# Spring2020V1_6.net
KiCad netlist of a schematic drawn in EAGLE
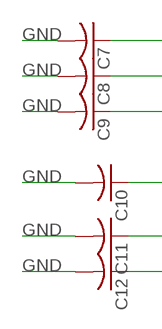
[diagram p0: schematic, sheet 1, part 1 of 2]
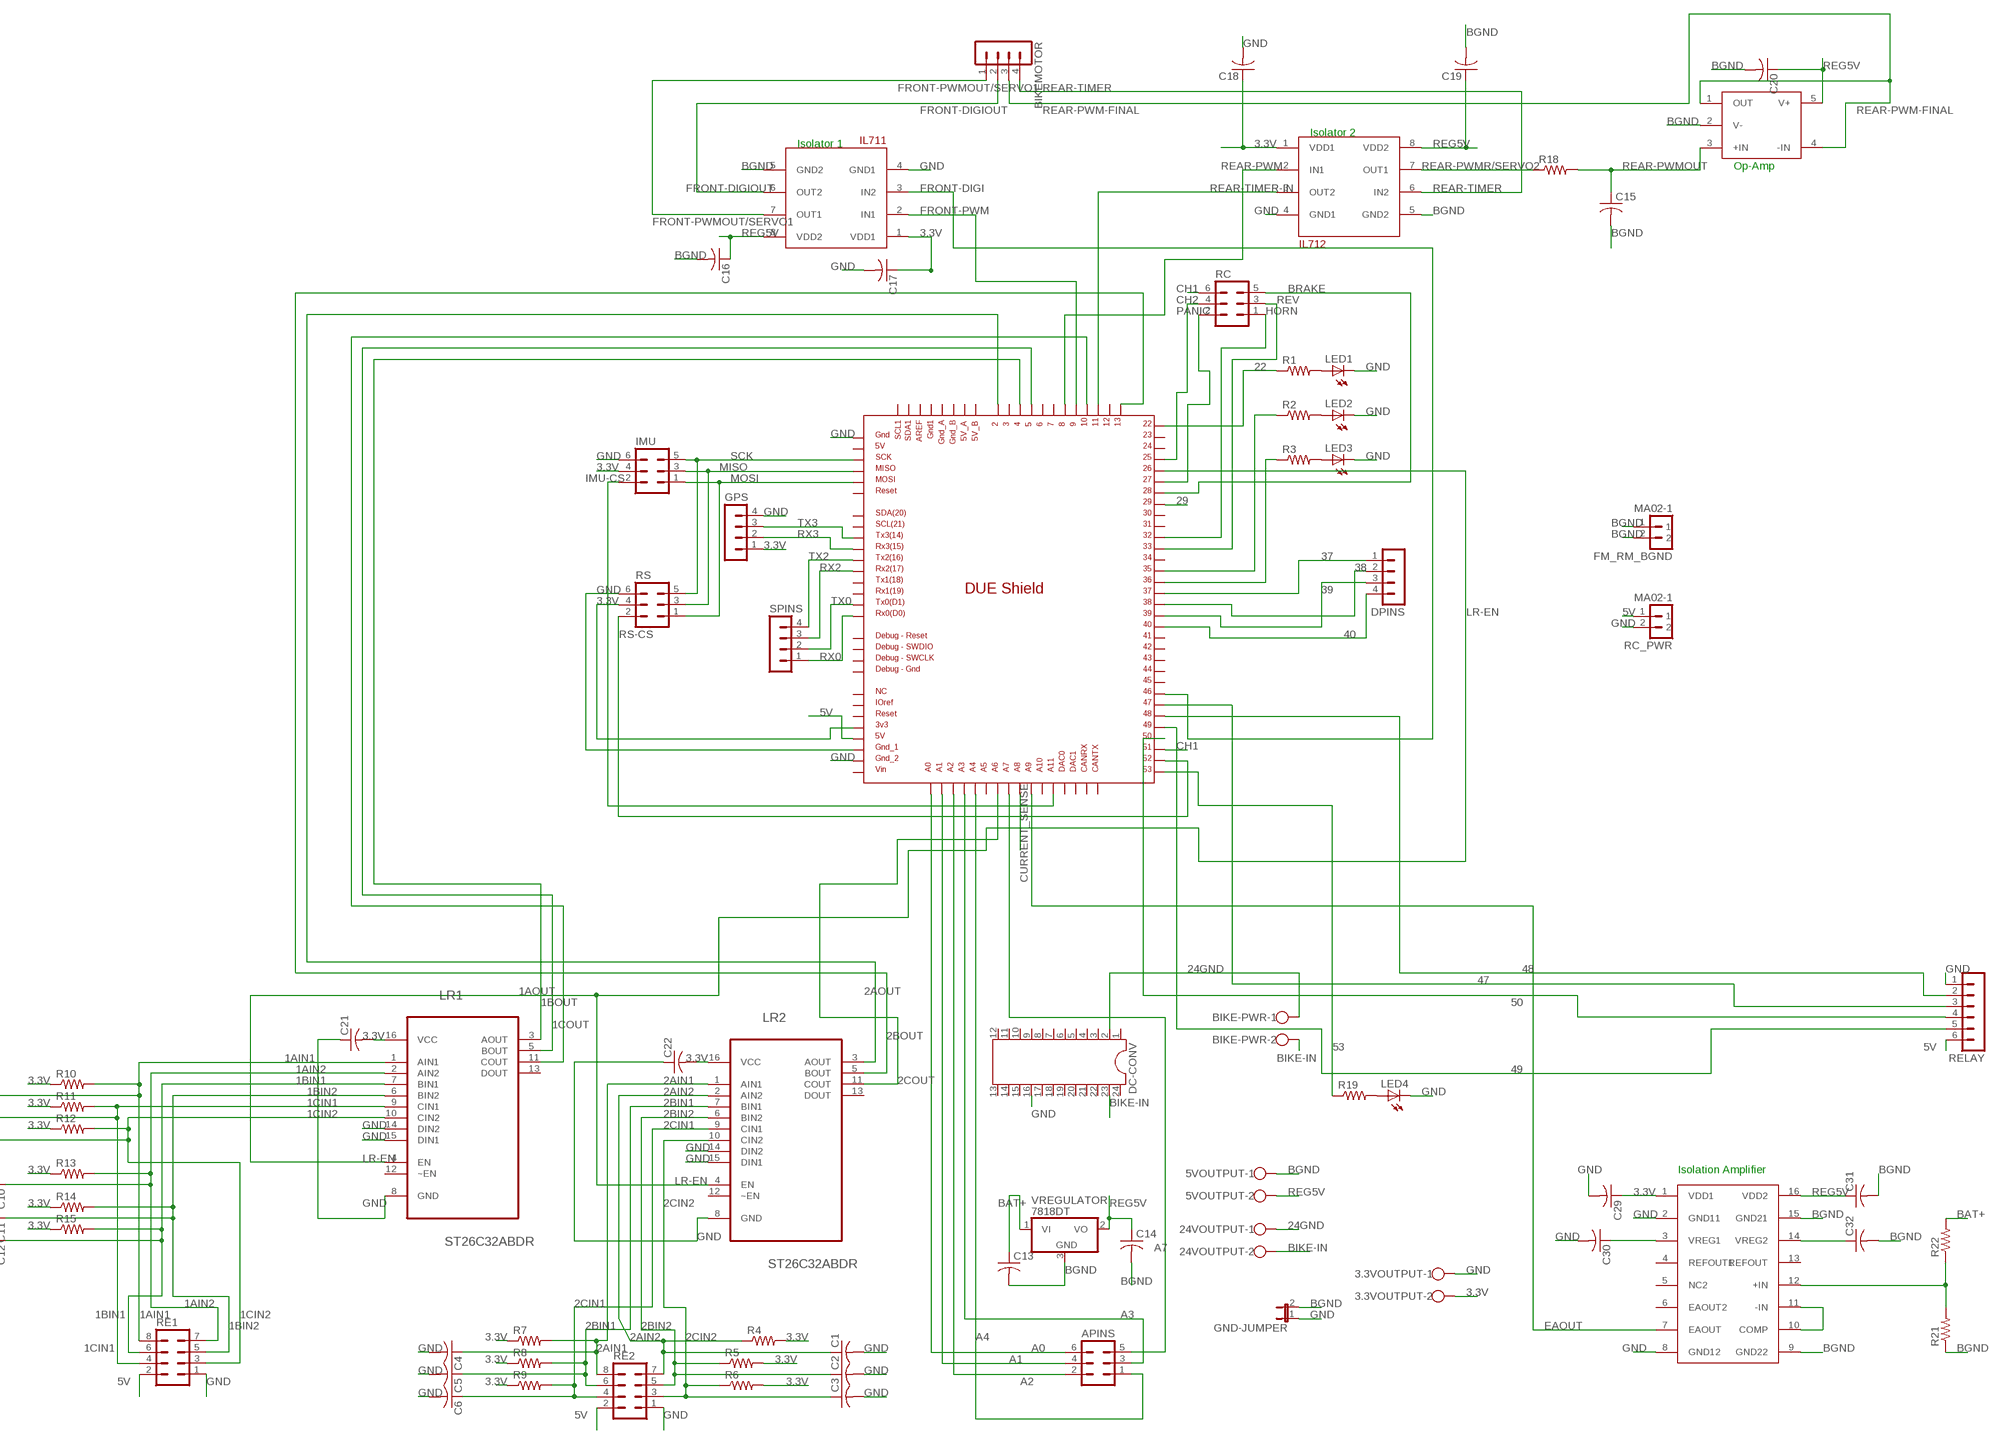
[diagram p1: schematic, sheet 1, part 2 of 2]

(export (version "E")
  (design (tool "Eeschema 10.0.6"))
  (components
    (comp (ref "3.3VOUTPUT")
      (value "W237-102")
      (footprint "eagle-import:W237-102")
      (fields (field (name "MPN") "237-102"))
      (libsource (lib "eagle-import") (part "W237-102"))
    )
    (comp (ref "5VOUTPUT")
      (value "W237-102")
      (footprint "eagle-import:W237-102")
      (fields (field (name "MPN") "237-102"))
      (libsource (lib "eagle-import") (part "W237-102"))
    )
    (comp (ref "24VOUTPUT")
      (value "W237-102")
      (footprint "eagle-import:W237-102")
      (fields (field (name "MPN") "237-102"))
      (libsource (lib "eagle-import") (part "W237-102"))
    )
    (comp (ref "APINS")
      (value "MA03-2")
      (footprint "eagle-import:MA03-2")
      (libsource (lib "eagle-import") (part "MA03-2"))
    )
    (comp (ref "BIKE-PWR")
      (value "W237-102")
      (footprint "eagle-import:W237-102")
      (fields (field (name "MPN") "237-102"))
      (libsource (lib "eagle-import") (part "W237-102"))
    )
    (comp (ref "BIKEMOTOR")
      (value "MA04-1")
      (footprint "eagle-import:MA04-1")
      (libsource (lib "eagle-import") (part "MA04-1"))
    )
    (comp (ref "C1")
      (value "C-US025-025X050")
      (footprint "eagle-import:C025-025X050")
      (libsource (lib "eagle-import") (part "C-US025-025X050"))
    )
    (comp (ref "C2")
      (value "C-US025-025X050")
      (footprint "eagle-import:C025-025X050")
      (libsource (lib "eagle-import") (part "C-US025-025X050"))
    )
    (comp (ref "C3")
      (value "C-US025-025X050")
      (footprint "eagle-import:C025-025X050")
      (libsource (lib "eagle-import") (part "C-US025-025X050"))
    )
    (comp (ref "C4")
      (value "C-US025-025X050")
      (footprint "eagle-import:C025-025X050")
      (libsource (lib "eagle-import") (part "C-US025-025X050"))
    )
    (comp (ref "C5")
      (value "C-US025-025X050")
      (footprint "eagle-import:C025-025X050")
      (libsource (lib "eagle-import") (part "C-US025-025X050"))
    )
    (comp (ref "C6")
      (value "C-US025-025X050")
      (footprint "eagle-import:C025-025X050")
      (libsource (lib "eagle-import") (part "C-US025-025X050"))
    )
    (comp (ref "C7")
      (value "C-US025-025X050")
      (footprint "eagle-import:C025-025X050")
      (libsource (lib "eagle-import") (part "C-US025-025X050"))
    )
    (comp (ref "C8")
      (value "C-US025-025X050")
      (footprint "eagle-import:C025-025X050")
      (libsource (lib "eagle-import") (part "C-US025-025X050"))
    )
    (comp (ref "C9")
      (value "C-US025-025X050")
      (footprint "eagle-import:C025-025X050")
      (libsource (lib "eagle-import") (part "C-US025-025X050"))
    )
    (comp (ref "C10")
      (value "C-US025-025X050")
      (footprint "eagle-import:C025-025X050")
      (libsource (lib "eagle-import") (part "C-US025-025X050"))
    )
    (comp (ref "C11")
      (value "C-US025-025X050")
      (footprint "eagle-import:C025-025X050")
      (libsource (lib "eagle-import") (part "C-US025-025X050"))
    )
    (comp (ref "C12")
      (value "C-US025-025X050")
      (footprint "eagle-import:C025-025X050")
      (libsource (lib "eagle-import") (part "C-US025-025X050"))
    )
    (comp (ref "C13")
      (value "C-US025-050X050")
      (footprint "eagle-import:C025-050X050")
      (libsource (lib "eagle-import") (part "C-US025-050X050"))
    )
    (comp (ref "C14")
      (value "C-US025-050X050")
      (footprint "eagle-import:C025-050X050")
      (libsource (lib "eagle-import") (part "C-US025-050X050"))
    )
    (comp (ref "C15")
      (value "C-US025-050X050")
      (footprint "eagle-import:C025-050X050")
      (libsource (lib "eagle-import") (part "C-US025-050X050"))
    )
    (comp (ref "C16")
      (value "C-US025-050X050")
      (footprint "eagle-import:C025-050X050")
      (libsource (lib "eagle-import") (part "C-US025-050X050"))
    )
    (comp (ref "C17")
      (value "C-US025-050X050")
      (footprint "eagle-import:C025-050X050")
      (libsource (lib "eagle-import") (part "C-US025-050X050"))
    )
    (comp (ref "C18")
      (value "C-US025-050X050")
      (footprint "eagle-import:C025-050X050")
      (libsource (lib "eagle-import") (part "C-US025-050X050"))
    )
    (comp (ref "C19")
      (value "C-US025-050X050")
      (footprint "eagle-import:C025-050X050")
      (libsource (lib "eagle-import") (part "C-US025-050X050"))
    )
    (comp (ref "C20")
      (value "C-US025-050X050")
      (footprint "eagle-import:C025-050X050")
      (libsource (lib "eagle-import") (part "C-US025-050X050"))
    )
    (comp (ref "C21")
      (value "C-US025-050X050")
      (footprint "eagle-import:C025-050X050")
      (libsource (lib "eagle-import") (part "C-US025-050X050"))
    )
    (comp (ref "C22")
      (value "C-US025-050X050")
      (footprint "eagle-import:C025-050X050")
      (libsource (lib "eagle-import") (part "C-US025-050X050"))
    )
    (comp (ref "C29")
      (value "C-US025-050X050")
      (footprint "eagle-import:C025-050X050")
      (libsource (lib "eagle-import") (part "C-US025-050X050"))
    )
    (comp (ref "C30")
      (value "C-US025-050X050")
      (footprint "eagle-import:C025-050X050")
      (libsource (lib "eagle-import") (part "C-US025-050X050"))
    )
    (comp (ref "C31")
      (value "C-US025-050X050")
      (footprint "eagle-import:C025-050X050")
      (libsource (lib "eagle-import") (part "C-US025-050X050"))
    )
    (comp (ref "C32")
      (value "C-US025-050X050")
      (footprint "eagle-import:C025-050X050")
      (libsource (lib "eagle-import") (part "C-US025-050X050"))
    )
    (comp (ref "DC-CONV")
      (value "CU.INC---VAWQ6-Q48-S12H-6")
      (footprint "eagle-import:DIL24-6")
      (libsource (lib "eagle-import") (part "CU.INC---VAWQ6-Q48-S12H-6"))
    )
    (comp (ref "DPINS")
      (value "MA04-1")
      (footprint "eagle-import:MA04-1")
      (libsource (lib "eagle-import") (part "MA04-1"))
    )
    (comp (ref "FM_RM_BGND")
      (value "MA02-1")
      (footprint "eagle-import:MA02-1")
      (libsource (lib "eagle-import") (part "MA02-1"))
    )
    (comp (ref "GND-JUMPER")
      (value "JP1E")
      (footprint "eagle-import:JP1")
      (libsource (lib "eagle-import") (part "JP1E"))
    )
    (comp (ref "GPS")
      (value "MA04-1")
      (footprint "eagle-import:MA04-1")
      (libsource (lib "eagle-import") (part "MA04-1"))
    )
    (comp (ref "IMU")
      (value "MA03-2")
      (footprint "eagle-import:MA03-2")
      (libsource (lib "eagle-import") (part "MA03-2"))
    )
    (comp (ref "LED1")
      (value "LED5MM")
      (footprint "eagle-import:LED5MM")
      (libsource (lib "eagle-import") (part "LED5MM"))
    )
    (comp (ref "LED2")
      (value "LED5MM")
      (footprint "eagle-import:LED5MM")
      (libsource (lib "eagle-import") (part "LED5MM"))
    )
    (comp (ref "LED3")
      (value "LED5MM")
      (footprint "eagle-import:LED5MM")
      (libsource (lib "eagle-import") (part "LED5MM"))
    )
    (comp (ref "LED4")
      (value "LED5MM")
      (footprint "eagle-import:LED5MM")
      (libsource (lib "eagle-import") (part "LED5MM"))
    )
    (comp (ref "LR1")
      (value "ST26C32ABDR")
      (footprint "eagle-import:SOIC127P600X175-16N")
      (libsource (lib "eagle-import") (part "ST26C32ABDR"))
    )
    (comp (ref "LR2")
      (value "ST26C32ABDR")
      (footprint "eagle-import:SOIC127P600X175-16N")
      (libsource (lib "eagle-import") (part "ST26C32ABDR"))
    )
    (comp (ref "OP-AMP")
      (value "OPAMP")
      (footprint "eagle-import:SOT95P280X145-5N")
      (libsource (lib "eagle-import") (part "OPAMP"))
    )
    (comp (ref "R1")
      (value "R-US_0309/10")
      (footprint "eagle-import:0309_10")
      (libsource (lib "eagle-import") (part "R-US_0309/10"))
    )
    (comp (ref "R2")
      (value "R-US_0309/10")
      (footprint "eagle-import:0309_10")
      (libsource (lib "eagle-import") (part "R-US_0309/10"))
    )
    (comp (ref "R3")
      (value "R-US_0309/10")
      (footprint "eagle-import:0309_10")
      (libsource (lib "eagle-import") (part "R-US_0309/10"))
    )
    (comp (ref "R4")
      (value "R-US_0613/15")
      (footprint "eagle-import:P0613_15")
      (libsource (lib "eagle-import") (part "resistor_R-US_0613/15"))
    )
    (comp (ref "R5")
      (value "R-US_0613/15")
      (footprint "eagle-import:P0613_15")
      (libsource (lib "eagle-import") (part "resistor_R-US_0613/15"))
    )
    (comp (ref "R6")
      (value "R-US_0613/15")
      (footprint "eagle-import:P0613_15")
      (libsource (lib "eagle-import") (part "resistor_R-US_0613/15"))
    )
    (comp (ref "R7")
      (value "R-US_0613/15")
      (footprint "eagle-import:P0613_15")
      (libsource (lib "eagle-import") (part "resistor_R-US_0613/15"))
    )
    (comp (ref "R8")
      (value "R-US_0613/15")
      (footprint "eagle-import:P0613_15")
      (libsource (lib "eagle-import") (part "resistor_R-US_0613/15"))
    )
    (comp (ref "R9")
      (value "R-US_0613/15")
      (footprint "eagle-import:P0613_15")
      (libsource (lib "eagle-import") (part "resistor_R-US_0613/15"))
    )
    (comp (ref "R10")
      (value "R-US_0613/15")
      (footprint "eagle-import:P0613_15")
      (libsource (lib "eagle-import") (part "resistor_R-US_0613/15"))
    )
    (comp (ref "R11")
      (value "R-US_0613/15")
      (footprint "eagle-import:P0613_15")
      (libsource (lib "eagle-import") (part "resistor_R-US_0613/15"))
    )
    (comp (ref "R12")
      (value "R-US_0613/15")
      (footprint "eagle-import:P0613_15")
      (libsource (lib "eagle-import") (part "resistor_R-US_0613/15"))
    )
    (comp (ref "R13")
      (value "R-US_0613/15")
      (footprint "eagle-import:P0613_15")
      (libsource (lib "eagle-import") (part "resistor_R-US_0613/15"))
    )
    (comp (ref "R14")
      (value "R-US_0613/15")
      (footprint "eagle-import:P0613_15")
      (libsource (lib "eagle-import") (part "resistor_R-US_0613/15"))
    )
    (comp (ref "R15")
      (value "R-US_0613/15")
      (footprint "eagle-import:P0613_15")
      (libsource (lib "eagle-import") (part "resistor_R-US_0613/15"))
    )
    (comp (ref "R18")
      (value "R-US_0414/15")
      (footprint "eagle-import:0414_15")
      (libsource (lib "eagle-import") (part "resistor_R-US_0414/15"))
    )
    (comp (ref "R19")
      (value "R-US_0309/10")
      (footprint "eagle-import:0309_10")
      (libsource (lib "eagle-import") (part "R-US_0309/10"))
    )
    (comp (ref "R21")
      (value "R-US_0414/15")
      (footprint "eagle-import:0414_15")
      (libsource (lib "eagle-import") (part "resistor_R-US_0414/15"))
    )
    (comp (ref "R22")
      (value "R-US_0414/15")
      (footprint "eagle-import:0414_15")
      (libsource (lib "eagle-import") (part "resistor_R-US_0414/15"))
    )
    (comp (ref "RC")
      (value "MA03-2")
      (footprint "eagle-import:MA03-2")
      (libsource (lib "eagle-import") (part "MA03-2"))
    )
    (comp (ref "RC_PWR")
      (value "MA02-1")
      (footprint "eagle-import:MA02-1")
      (libsource (lib "eagle-import") (part "MA02-1"))
    )
    (comp (ref "RE1")
      (value "MA04-2")
      (footprint "eagle-import:MA04-2")
      (libsource (lib "eagle-import") (part "MA04-2"))
    )
    (comp (ref "RE2")
      (value "MA04-2")
      (footprint "eagle-import:MA04-2")
      (libsource (lib "eagle-import") (part "MA04-2"))
    )
    (comp (ref "RELAY")
      (value "MA06-1")
      (footprint "eagle-import:MA06-1")
      (libsource (lib "eagle-import") (part "MA06-1"))
    )
    (comp (ref "RS")
      (value "MA03-2")
      (footprint "eagle-import:MA03-2")
      (libsource (lib "eagle-import") (part "MA03-2"))
    )
    (comp (ref "SPINS")
      (value "MA04-1")
      (footprint "eagle-import:MA04-1")
      (libsource (lib "eagle-import") (part "MA04-1"))
    )
    (comp (ref "U$1")
      (value "DUE(NORMAL)")
      (footprint "eagle-import:DUE(NORMAL)")
      (libsource (lib "eagle-import") (part "DUE(NORMAL)"))
    )
    (comp (ref "U$2")
      (value "IL-711")
      (footprint "eagle-import:8PINSOIC")
      (libsource (lib "eagle-import") (part "IL-711"))
    )
    (comp (ref "U$5")
      (value "ISOLATED_ERROR_AMP_ADUM3190")
      (footprint "eagle-import:QSOP16")
      (libsource (lib "eagle-import") (part "ISOLATED_ERROR_AMP_ADUM3190"))
    )
    (comp (ref "U$7")
      (value "IL-712")
      (footprint "eagle-import:8PINSOIC")
      (libsource (lib "eagle-import") (part "IL-712"))
    )
    (comp (ref "VREGULATOR")
      (value "7818DT")
      (footprint "eagle-import:TO252")
      (libsource (lib "eagle-import") (part "78DT18"))
    )
  )
  (nets
    (net (code "1") (name "/1AIN1") (class "Default")
      (node (ref "C7") (pin "1") (pinfunction "1_1") (pintype "passive"))
      (node (ref "LR1") (pin "1") (pinfunction "AIN1_1") (pintype "input"))
      (node (ref "R10") (pin "2") (pinfunction "2_2") (pintype "passive"))
      (node (ref "RE1") (pin "8") (pinfunction "8_8") (pintype "passive"))
    )
    (net (code "2") (name "/1AIN2") (class "Default")
      (node (ref "C10") (pin "1") (pinfunction "1_1") (pintype "passive"))
      (node (ref "LR1") (pin "2") (pinfunction "AIN2_2") (pintype "input"))
      (node (ref "R13") (pin "2") (pinfunction "2_2") (pintype "passive"))
      (node (ref "RE1") (pin "7") (pinfunction "7_7") (pintype "passive"))
    )
    (net (code "3") (name "/1AOUT") (class "Default")
      (node (ref "LR1") (pin "3") (pinfunction "AOUT_3") (pintype "output"))
      (node (ref "U$1") (pin "4") (pinfunction "4_4") (pintype "bidirectional"))
    )
    (net (code "4") (name "/1BIN1") (class "Default")
      (node (ref "C12") (pin "1") (pinfunction "1_1") (pintype "passive"))
      (node (ref "LR1") (pin "7") (pinfunction "BIN1_7") (pintype "input"))
      (node (ref "R15") (pin "2") (pinfunction "2_2") (pintype "passive"))
      (node (ref "RE1") (pin "6") (pinfunction "6_6") (pintype "passive"))
    )
    (net (code "5") (name "/1BIN2") (class "Default")
      (node (ref "C11") (pin "1") (pinfunction "1_1") (pintype "passive"))
      (node (ref "LR1") (pin "6") (pinfunction "BIN2_6") (pintype "input"))
      (node (ref "R14") (pin "2") (pinfunction "2_2") (pintype "passive"))
      (node (ref "RE1") (pin "5") (pinfunction "5_5") (pintype "passive"))
    )
    (net (code "6") (name "/1BOUT") (class "Default")
      (node (ref "LR1") (pin "5") (pinfunction "BOUT_5") (pintype "output"))
      (node (ref "U$1") (pin "5") (pinfunction "5_5") (pintype "bidirectional"))
    )
    (net (code "7") (name "/1CIN1") (class "Default")
      (node (ref "C8") (pin "1") (pinfunction "1_1") (pintype "passive"))
      (node (ref "LR1") (pin "9") (pinfunction "CIN1_9") (pintype "input"))
      (node (ref "R11") (pin "2") (pinfunction "2_2") (pintype "passive"))
      (node (ref "RE1") (pin "4") (pinfunction "4_4") (pintype "passive"))
    )
    (net (code "8") (name "/1CIN2") (class "Default")
      (node (ref "C9") (pin "1") (pinfunction "1_1") (pintype "passive"))
      (node (ref "LR1") (pin "10") (pinfunction "CIN2_10") (pintype "input"))
      (node (ref "R12") (pin "2") (pinfunction "2_2") (pintype "passive"))
      (node (ref "RE1") (pin "3") (pinfunction "3_3") (pintype "passive"))
    )
    (net (code "9") (name "/1COUT") (class "Default")
      (node (ref "LR1") (pin "11") (pinfunction "COUT_11") (pintype "output"))
      (node (ref "U$1") (pin "10") (pinfunction "10_10") (pintype "bidirectional"))
    )
    (net (code "10") (name "/2AIN1") (class "Default")
      (node (ref "C4") (pin "1") (pinfunction "1_1") (pintype "passive"))
      (node (ref "LR2") (pin "1") (pinfunction "AIN1_1") (pintype "input"))
      (node (ref "R7") (pin "2") (pinfunction "2_2") (pintype "passive"))
      (node (ref "RE2") (pin "8") (pinfunction "8_8") (pintype "passive"))
    )
    (net (code "11") (name "/2AIN2") (class "Default")
      (node (ref "C1") (pin "1") (pinfunction "1_1") (pintype "passive"))
      (node (ref "LR2") (pin "2") (pinfunction "AIN2_2") (pintype "input"))
      (node (ref "R4") (pin "1") (pinfunction "1_1") (pintype "passive"))
      (node (ref "RE2") (pin "7") (pinfunction "7_7") (pintype "passive"))
    )
    (net (code "12") (name "/2AOUT") (class "Default")
      (node (ref "LR2") (pin "3") (pinfunction "AOUT_3") (pintype "output"))
      (node (ref "U$1") (pin "2") (pinfunction "2_2") (pintype "bidirectional"))
    )
    (net (code "13") (name "/2BIN1") (class "Default")
      (node (ref "C5") (pin "1") (pinfunction "1_1") (pintype "passive"))
      (node (ref "LR2") (pin "7") (pinfunction "BIN1_7") (pintype "input"))
      (node (ref "R8") (pin "2") (pinfunction "2_2") (pintype "passive"))
      (node (ref "RE2") (pin "6") (pinfunction "6_6") (pintype "passive"))
    )
    (net (code "14") (name "/2BIN2") (class "Default")
      (node (ref "C2") (pin "1") (pinfunction "1_1") (pintype "passive"))
      (node (ref "LR2") (pin "6") (pinfunction "BIN2_6") (pintype "input"))
      (node (ref "R5") (pin "1") (pinfunction "1_1") (pintype "passive"))
      (node (ref "RE2") (pin "5") (pinfunction "5_5") (pintype "passive"))
    )
    (net (code "15") (name "/2BOUT") (class "Default")
      (node (ref "LR2") (pin "5") (pinfunction "BOUT_5") (pintype "output"))
      (node (ref "U$1") (pin "13") (pinfunction "13_13") (pintype "bidirectional"))
    )
    (net (code "16") (name "/2CIN1") (class "Default")
      (node (ref "C6") (pin "1") (pinfunction "1_1") (pintype "passive"))
      (node (ref "LR2") (pin "9") (pinfunction "CIN1_9") (pintype "input"))
      (node (ref "R9") (pin "2") (pinfunction "2_2") (pintype "passive"))
      (node (ref "RE2") (pin "4") (pinfunction "4_4") (pintype "passive"))
    )
    (net (code "17") (name "/2CIN2") (class "Default")
      (node (ref "C3") (pin "1") (pinfunction "1_1") (pintype "passive"))
      (node (ref "LR2") (pin "10") (pinfunction "CIN2_10") (pintype "input"))
      (node (ref "R6") (pin "1") (pinfunction "1_1") (pintype "passive"))
      (node (ref "RE2") (pin "3") (pinfunction "3_3") (pintype "passive"))
    )
    (net (code "18") (name "/2COUT") (class "Default")
      (node (ref "LR2") (pin "11") (pinfunction "COUT_11") (pintype "output"))
      (node (ref "U$1") (pin "A6") (pinfunction "A6_A6") (pintype "bidirectional"))
    )
    (net (code "19") (name "/3.3V") (class "Default")
      (node (ref "3.3VOUTPUT") (pin "2") (pinfunction "KL_2") (pintype "passive"))
      (node (ref "C17") (pin "1") (pinfunction "1_1") (pintype "passive"))
      (node (ref "C18") (pin "1") (pinfunction "1_1") (pintype "passive"))
      (node (ref "C21") (pin "2") (pinfunction "2_2") (pintype "passive"))
      (node (ref "C22") (pin "2") (pinfunction "2_2") (pintype "passive"))
      (node (ref "C29") (pin "1") (pinfunction "1_1") (pintype "passive"))
      (node (ref "GPS") (pin "1") (pinfunction "1_1") (pintype "passive"))
      (node (ref "IMU") (pin "4") (pinfunction "4_4") (pintype "passive"))
      (node (ref "LR1") (pin "16") (pinfunction "VCC_16") (pintype "power_in"))
      (node (ref "LR2") (pin "16") (pinfunction "VCC_16") (pintype "power_in"))
      (node (ref "R10") (pin "1") (pinfunction "1_1") (pintype "passive"))
      (node (ref "R11") (pin "1") (pinfunction "1_1") (pintype "passive"))
      (node (ref "R12") (pin "1") (pinfunction "1_1") (pintype "passive"))
      (node (ref "R13") (pin "1") (pinfunction "1_1") (pintype "passive"))
      (node (ref "R14") (pin "1") (pinfunction "1_1") (pintype "passive"))
      (node (ref "R15") (pin "1") (pinfunction "1_1") (pintype "passive"))
      (node (ref "R4") (pin "2") (pinfunction "2_2") (pintype "passive"))
      (node (ref "R5") (pin "2") (pinfunction "2_2") (pintype "passive"))
      (node (ref "R6") (pin "2") (pinfunction "2_2") (pintype "passive"))
      (node (ref "R7") (pin "1") (pinfunction "1_1") (pintype "passive"))
      (node (ref "R8") (pin "1") (pinfunction "1_1") (pintype "passive"))
      (node (ref "R9") (pin "1") (pinfunction "1_1") (pintype "passive"))
      (node (ref "RS") (pin "4") (pinfunction "4_4") (pintype "passive"))
      (node (ref "U$1") (pin "3V3") (pinfunction "3V3_3V3") (pintype "bidirectional"))
      (node (ref "U$2") (pin "1") (pinfunction "VDD1_1") (pintype "power_in"))
      (node (ref "U$5") (pin "1") (pinfunction "VDD1_1") (pintype "bidirectional"))
      (node (ref "U$7") (pin "1") (pinfunction "VDD1_1") (pintype "power_in"))
    )
    (net (code "20") (name "/5V") (class "Default")
      (node (ref "RC_PWR") (pin "1") (pinfunction "1_1") (pintype "passive"))
      (node (ref "RE1") (pin "2") (pinfunction "2_2") (pintype "passive"))
      (node (ref "RE2") (pin "2") (pinfunction "2_2") (pintype "passive"))
      (node (ref "RELAY") (pin "6") (pinfunction "6_6") (pintype "passive"))
      (node (ref "U$1") (pin "5V") (pinfunction "5V_5V") (pintype "bidirectional"))
    )
    (net (code "21") (name "/22") (class "Default")
      (node (ref "R1") (pin "1") (pinfunction "1_1") (pintype "passive"))
      (node (ref "U$1") (pin "22") (pinfunction "22_22") (pintype "bidirectional"))
    )
    (net (code "22") (name "/24GND") (class "Default")
      (node (ref "24VOUTPUT") (pin "1") (pinfunction "KL_1") (pintype "passive"))
      (node (ref "BIKE-PWR") (pin "1") (pinfunction "KL_1") (pintype "passive"))
      (node (ref "DC-CONV") (pin "2") (pinfunction "2_2") (pintype "passive"))
    )
    (net (code "23") (name "/29") (class "Default")
      (node (ref "U$1") (pin "29") (pinfunction "29_29") (pintype "bidirectional"))
    )
    (net (code "24") (name "/37") (class "Default")
      (node (ref "DPINS") (pin "1") (pinfunction "1_1") (pintype "passive"))
      (node (ref "U$1") (pin "37") (pinfunction "37_37") (pintype "bidirectional"))
    )
    (net (code "25") (name "/38") (class "Default")
      (node (ref "DPINS") (pin "2") (pinfunction "2_2") (pintype "passive"))
      (node (ref "U$1") (pin "38") (pinfunction "38_38") (pintype "bidirectional"))
    )
    (net (code "26") (name "/39") (class "Default")
      (node (ref "DPINS") (pin "3") (pinfunction "3_3") (pintype "passive"))
      (node (ref "U$1") (pin "39") (pinfunction "39_39") (pintype "bidirectional"))
    )
    (net (code "27") (name "/40") (class "Default")
      (node (ref "DPINS") (pin "4") (pinfunction "4_4") (pintype "passive"))
      (node (ref "U$1") (pin "40") (pinfunction "40_40") (pintype "bidirectional"))
    )
    (net (code "28") (name "/47") (class "Default")
      (node (ref "RELAY") (pin "3") (pinfunction "3_3") (pintype "passive"))
      (node (ref "U$1") (pin "47") (pinfunction "47_47") (pintype "bidirectional"))
    )
    (net (code "29") (name "/48") (class "Default")
      (node (ref "RELAY") (pin "2") (pinfunction "2_2") (pintype "passive"))
      (node (ref "U$1") (pin "48") (pinfunction "48_48") (pintype "bidirectional"))
    )
    (net (code "30") (name "/49") (class "Default")
      (node (ref "RELAY") (pin "5") (pinfunction "5_5") (pintype "passive"))
      (node (ref "U$1") (pin "49") (pinfunction "49_49") (pintype "bidirectional"))
    )
    (net (code "31") (name "/50") (class "Default")
      (node (ref "RELAY") (pin "4") (pinfunction "4_4") (pintype "passive"))
      (node (ref "U$1") (pin "50") (pinfunction "50_50") (pintype "bidirectional"))
    )
    (net (code "32") (name "/53") (class "Default")
      (node (ref "R19") (pin "1") (pinfunction "1_1") (pintype "passive"))
      (node (ref "U$1") (pin "53") (pinfunction "53_53") (pintype "bidirectional"))
    )
    (net (code "33") (name "/A0") (class "Default")
      (node (ref "APINS") (pin "6") (pinfunction "6_6") (pintype "passive"))
      (node (ref "U$1") (pin "A0") (pinfunction "A0_A0") (pintype "bidirectional"))
    )
    (net (code "34") (name "/A1") (class "Default")
      (node (ref "APINS") (pin "4") (pinfunction "4_4") (pintype "passive"))
      (node (ref "U$1") (pin "A1") (pinfunction "A1_A1") (pintype "bidirectional"))
    )
    (net (code "35") (name "/A2") (class "Default")
      (node (ref "APINS") (pin "2") (pinfunction "2_2") (pintype "passive"))
      (node (ref "U$1") (pin "A2") (pinfunction "A2_A2") (pintype "bidirectional"))
    )
    (net (code "36") (name "/A3") (class "Default")
      (node (ref "APINS") (pin "3") (pinfunction "3_3") (pintype "passive"))
      (node (ref "U$1") (pin "A3") (pinfunction "A3_A3") (pintype "bidirectional"))
    )
    (net (code "37") (name "/A4") (class "Default")
      (node (ref "APINS") (pin "1") (pinfunction "1_1") (pintype "passive"))
      (node (ref "U$1") (pin "A4") (pinfunction "A4_A4") (pintype "bidirectional"))
    )
    (net (code "38") (name "/A7") (class "Default")
      (node (ref "APINS") (pin "5") (pinfunction "5_5") (pintype "passive"))
      (node (ref "U$1") (pin "A7") (pinfunction "A7_A7") (pintype "bidirectional"))
    )
    (net (code "39") (name "/BAT+") (class "Default")
      (node (ref "C13") (pin "1") (pinfunction "1_1") (pintype "passive"))
      (node (ref "R22") (pin "2") (pinfunction "2_2") (pintype "passive"))
      (node (ref "VREGULATOR") (pin "1") (pinfunction "VI_1") (pintype "input"))
    )
    (net (code "40") (name "/BGND") (class "Default")
      (node (ref "5VOUTPUT") (pin "1") (pinfunction "KL_1") (pintype "passive"))
      (node (ref "C13") (pin "2") (pinfunction "2_2") (pintype "passive"))
      (node (ref "C14") (pin "2") (pinfunction "2_2") (pintype "passive"))
      (node (ref "C15") (pin "2") (pinfunction "2_2") (pintype "passive"))
      (node (ref "C16") (pin "2") (pinfunction "2_2") (pintype "passive"))
      (node (ref "C19") (pin "2") (pinfunction "2_2") (pintype "passive"))
      (node (ref "C20") (pin "2") (pinfunction "2_2") (pintype "passive"))
      (node (ref "C31") (pin "2") (pinfunction "2_2") (pintype "passive"))
      (node (ref "C32") (pin "2") (pinfunction "2_2") (pintype "passive"))
      (node (ref "FM_RM_BGND") (pin "1") (pinfunction "1_1") (pintype "passive"))
      (node (ref "FM_RM_BGND") (pin "2") (pinfunction "2_2") (pintype "passive"))
      (node (ref "GND-JUMPER") (pin "2") (pinfunction "2_2") (pintype "passive"))
      (node (ref "OP-AMP") (pin "2") (pinfunction "V-_2") (pintype "output"))
      (node (ref "R21") (pin "1") (pinfunction "1_1") (pintype "passive"))
      (node (ref "U$2") (pin "5") (pinfunction "GND2_5") (pintype "power_in"))
      (node (ref "U$5") (pin "15") (pinfunction "GND21_15") (pintype "bidirectional"))
      (node (ref "U$5") (pin "9") (pinfunction "GND22_9") (pintype "bidirectional"))
      (node (ref "U$7") (pin "5") (pinfunction "GND2_5") (pintype "power_in"))
      (node (ref "VREGULATOR") (pin "3") (pinfunction "GND_3") (pintype "passive"))
    )
    (net (code "41") (name "/BIKE-IN") (class "Default")
      (node (ref "24VOUTPUT") (pin "2") (pinfunction "KL_2") (pintype "passive"))
      (node (ref "BIKE-PWR") (pin "2") (pinfunction "KL_2") (pintype "passive"))
      (node (ref "DC-CONV") (pin "23") (pinfunction "23_23") (pintype "passive"))
    )
    (net (code "42") (name "/BRAKE") (class "Default")
      (node (ref "RC") (pin "5") (pinfunction "5_5") (pintype "passive"))
      (node (ref "U$1") (pin "28") (pinfunction "28_28") (pintype "bidirectional"))
    )
    (net (code "43") (name "/CH1") (class "Default")
      (node (ref "RC") (pin "6") (pinfunction "6_6") (pintype "passive"))
      (node (ref "U$1") (pin "51") (pinfunction "51_51") (pintype "bidirectional"))
    )
    (net (code "44") (name "/CH2") (class "Default")
      (node (ref "RC") (pin "4") (pinfunction "4_4") (pintype "passive"))
      (node (ref "U$1") (pin "25") (pinfunction "25_25") (pintype "bidirectional"))
    )
    (net (code "45") (name "/CURRENT_SENSE") (class "Default")
      (node (ref "U$1") (pin "A8") (pinfunction "A8_A8") (pintype "bidirectional"))
    )
    (net (code "46") (name "/EAOUT") (class "Default")
      (node (ref "U$1") (pin "A9") (pinfunction "A9_A9") (pintype "bidirectional"))
      (node (ref "U$5") (pin "7") (pinfunction "EAOUT_7") (pintype "bidirectional"))
    )
    (net (code "47") (name "/FRONT-DIGI") (class "Default")
      (node (ref "U$1") (pin "46") (pinfunction "46_46") (pintype "bidirectional"))
      (node (ref "U$2") (pin "3") (pinfunction "IN2_3") (pintype "input"))
    )
    (net (code "48") (name "/FRONT-DIGIOUT") (class "Default")
      (node (ref "BIKEMOTOR") (pin "2") (pinfunction "2_2") (pintype "passive"))
      (node (ref "U$2") (pin "6") (pinfunction "OUT2_6") (pintype "output"))
    )
    (net (code "49") (name "/FRONT-PWM") (class "Default")
      (node (ref "U$1") (pin "9") (pinfunction "9_9") (pintype "bidirectional"))
      (node (ref "U$2") (pin "2") (pinfunction "IN1_2") (pintype "input"))
    )
    (net (code "50") (name "/FRONT-PWMOUT{slash}SERVO1") (class "Default")
      (node (ref "BIKEMOTOR") (pin "1") (pinfunction "1_1") (pintype "passive"))
      (node (ref "U$2") (pin "7") (pinfunction "OUT1_7") (pintype "output"))
    )
    (net (code "51") (name "/GND") (class "Default")
      (node (ref "3.3VOUTPUT") (pin "1") (pinfunction "KL_1") (pintype "passive"))
      (node (ref "C1") (pin "2") (pinfunction "2_2") (pintype "passive"))
      (node (ref "C10") (pin "2") (pinfunction "2_2") (pintype "passive"))
      (node (ref "C11") (pin "2") (pinfunction "2_2") (pintype "passive"))
      (node (ref "C12") (pin "2") (pinfunction "2_2") (pintype "passive"))
      (node (ref "C17") (pin "2") (pinfunction "2_2") (pintype "passive"))
      (node (ref "C18") (pin "2") (pinfunction "2_2") (pintype "passive"))
      (node (ref "C2") (pin "2") (pinfunction "2_2") (pintype "passive"))
      (node (ref "C21") (pin "1") (pinfunction "1_1") (pintype "passive"))
      (node (ref "C22") (pin "1") (pinfunction "1_1") (pintype "passive"))
      (node (ref "C29") (pin "2") (pinfunction "2_2") (pintype "passive"))
      (node (ref "C3") (pin "2") (pinfunction "2_2") (pintype "passive"))
      (node (ref "C30") (pin "2") (pinfunction "2_2") (pintype "passive"))
      (node (ref "C4") (pin "2") (pinfunction "2_2") (pintype "passive"))
      (node (ref "C5") (pin "2") (pinfunction "2_2") (pintype "passive"))
      (node (ref "C6") (pin "2") (pinfunction "2_2") (pintype "passive"))
      (node (ref "C7") (pin "2") (pinfunction "2_2") (pintype "passive"))
      (node (ref "C8") (pin "2") (pinfunction "2_2") (pintype "passive"))
      (node (ref "C9") (pin "2") (pinfunction "2_2") (pintype "passive"))
      (node (ref "DC-CONV") (pin "16") (pinfunction "16_16") (pintype "passive"))
      (node (ref "GND-JUMPER") (pin "1") (pinfunction "1_1") (pintype "passive"))
      (node (ref "GPS") (pin "4") (pinfunction "4_4") (pintype "passive"))
      (node (ref "IMU") (pin "6") (pinfunction "6_6") (pintype "passive"))
      (node (ref "LED1") (pin "K") (pinfunction "C_K") (pintype "passive"))
      (node (ref "LED2") (pin "K") (pinfunction "C_K") (pintype "passive"))
      (node (ref "LED3") (pin "K") (pinfunction "C_K") (pintype "passive"))
      (node (ref "LED4") (pin "K") (pinfunction "C_K") (pintype "passive"))
      (node (ref "LR1") (pin "14") (pinfunction "DIN2_14") (pintype "input"))
      (node (ref "LR1") (pin "15") (pinfunction "DIN1_15") (pintype "input"))
      (node (ref "LR1") (pin "8") (pinfunction "GND_8") (pintype "passive"))
      (node (ref "LR2") (pin "14") (pinfunction "DIN2_14") (pintype "input"))
      (node (ref "LR2") (pin "15") (pinfunction "DIN1_15") (pintype "input"))
      (node (ref "LR2") (pin "8") (pinfunction "GND_8") (pintype "passive"))
      (node (ref "RC_PWR") (pin "2") (pinfunction "2_2") (pintype "passive"))
      (node (ref "RE1") (pin "1") (pinfunction "1_1") (pintype "passive"))
      (node (ref "RE2") (pin "1") (pinfunction "1_1") (pintype "passive"))
      (node (ref "RELAY") (pin "1") (pinfunction "1_1") (pintype "passive"))
      (node (ref "RS") (pin "6") (pinfunction "6_6") (pintype "passive"))
      (node (ref "U$1") (pin "5V_ICSP") (pinfunction "5V_ICSP_5V_ICSP") (pintype "bidirectional"))
      (node (ref "U$1") (pin "GND_1") (pinfunction "GND_1_GND_1") (pintype "bidirectional"))
      (node (ref "U$1") (pin "GND_2") (pinfunction "GND_2_GND_2") (pintype "bidirectional"))
      (node (ref "U$2") (pin "4") (pinfunction "GND1_4") (pintype "power_in"))
      (node (ref "U$5") (pin "2") (pinfunction "GND11_2") (pintype "bidirectional"))
      (node (ref "U$5") (pin "8") (pinfunction "GND12_8") (pintype "bidirectional"))
      (node (ref "U$7") (pin "4") (pinfunction "GND1_4") (pintype "power_in"))
    )
    (net (code "52") (name "/HORN") (class "Default")
      (node (ref "RC") (pin "1") (pinfunction "1_1") (pintype "passive"))
      (node (ref "U$1") (pin "32") (pinfunction "32_32") (pintype "bidirectional"))
    )
    (net (code "53") (name "/IMU-CS") (class "Default")
      (node (ref "IMU") (pin "2") (pinfunction "2_2") (pintype "passive"))
      (node (ref "U$1") (pin "A11") (pinfunction "A11_A11") (pintype "bidirectional"))
    )
    (net (code "54") (name "/LR-EN") (class "Default")
      (node (ref "LR1") (pin "4") (pinfunction "EN_4") (pintype "input"))
      (node (ref "LR2") (pin "4") (pinfunction "EN_4") (pintype "input"))
      (node (ref "U$1") (pin "26") (pinfunction "26_26") (pintype "bidirectional"))
    )
    (net (code "55") (name "/MISO") (class "Default")
      (node (ref "IMU") (pin "3") (pinfunction "3_3") (pintype "passive"))
      (node (ref "RS") (pin "3") (pinfunction "3_3") (pintype "passive"))
      (node (ref "U$1") (pin "MISO_ICSP") (pinfunction "MISO_ICSP_MISO_ICSP") (pintype "bidirectional"))
    )
    (net (code "56") (name "/MOSI") (class "Default")
      (node (ref "IMU") (pin "1") (pinfunction "1_1") (pintype "passive"))
      (node (ref "RS") (pin "1") (pinfunction "1_1") (pintype "passive"))
      (node (ref "U$1") (pin "MOSI_ICSP") (pinfunction "MOSI_ICSP_MOSI_ICSP") (pintype "bidirectional"))
    )
    (net (code "57") (name "/PANIC") (class "Default")
      (node (ref "RC") (pin "2") (pinfunction "2_2") (pintype "passive"))
      (node (ref "U$1") (pin "27") (pinfunction "27_27") (pintype "bidirectional"))
    )
    (net (code "58") (name "/REAR-PWM") (class "Default")
      (node (ref "U$1") (pin "8") (pinfunction "8_8") (pintype "bidirectional"))
      (node (ref "U$7") (pin "2") (pinfunction "IN1_2") (pintype "input"))
    )
    (net (code "59") (name "/REAR-PWM-FINAL") (class "Default")
      (node (ref "BIKEMOTOR") (pin "3") (pinfunction "3_3") (pintype "passive"))
      (node (ref "OP-AMP") (pin "1") (pinfunction "OUT_1") (pintype "output"))
      (node (ref "OP-AMP") (pin "4") (pinfunction "-IN_4") (pintype "input"))
    )
    (net (code "60") (name "/REAR-PWMOUT") (class "Default")
      (node (ref "C15") (pin "1") (pinfunction "1_1") (pintype "passive"))
      (node (ref "OP-AMP") (pin "3") (pinfunction "+IN_3") (pintype "input"))
      (node (ref "R18") (pin "2") (pinfunction "2_2") (pintype "passive"))
    )
    (net (code "61") (name "/REAR-PWMR{slash}SERVO2") (class "Default")
      (node (ref "R18") (pin "1") (pinfunction "1_1") (pintype "passive"))
      (node (ref "U$7") (pin "7") (pinfunction "OUT1_7") (pintype "output"))
    )
    (net (code "62") (name "/REAR-TIMER") (class "Default")
      (node (ref "BIKEMOTOR") (pin "4") (pinfunction "4_4") (pintype "passive"))
      (node (ref "U$7") (pin "6") (pinfunction "IN2_6") (pintype "input"))
    )
    (net (code "63") (name "/REAR-TIMER-IN") (class "Default")
      (node (ref "U$1") (pin "11") (pinfunction "11_11") (pintype "bidirectional"))
      (node (ref "U$7") (pin "3") (pinfunction "OUT2_3") (pintype "output"))
    )
    (net (code "64") (name "/REG5V") (class "Default")
      (node (ref "5VOUTPUT") (pin "2") (pinfunction "KL_2") (pintype "passive"))
      (node (ref "C14") (pin "1") (pinfunction "1_1") (pintype "passive"))
      (node (ref "C16") (pin "1") (pinfunction "1_1") (pintype "passive"))
      (node (ref "C19") (pin "1") (pinfunction "1_1") (pintype "passive"))
      (node (ref "C20") (pin "1") (pinfunction "1_1") (pintype "passive"))
      (node (ref "C31") (pin "1") (pinfunction "1_1") (pintype "passive"))
      (node (ref "OP-AMP") (pin "5") (pinfunction "V+_5") (pintype "power_in"))
      (node (ref "U$2") (pin "8") (pinfunction "VDD2_8") (pintype "power_in"))
      (node (ref "U$5") (pin "16") (pinfunction "VDD2_16") (pintype "bidirectional"))
      (node (ref "U$7") (pin "8") (pinfunction "VDD2_8") (pintype "power_in"))
      (node (ref "VREGULATOR") (pin "2") (pinfunction "VO_2") (pintype "passive"))
    )
    (net (code "65") (name "/REV") (class "Default")
      (node (ref "RC") (pin "3") (pinfunction "3_3") (pintype "passive"))
      (node (ref "U$1") (pin "33") (pinfunction "33_33") (pintype "bidirectional"))
    )
    (net (code "66") (name "/RS-CS") (class "Default")
      (node (ref "RS") (pin "2") (pinfunction "2_2") (pintype "passive"))
      (node (ref "U$1") (pin "52") (pinfunction "52_52") (pintype "bidirectional"))
    )
    (net (code "67") (name "/RX0") (class "Default")
      (node (ref "SPINS") (pin "1") (pinfunction "1_1") (pintype "passive"))
      (node (ref "U$1") (pin "RX0") (pinfunction "RX0_RX0") (pintype "bidirectional"))
    )
    (net (code "68") (name "/RX2") (class "Default")
      (node (ref "SPINS") (pin "3") (pinfunction "3_3") (pintype "passive"))
      (node (ref "U$1") (pin "RX2") (pinfunction "RX2_RX2") (pintype "bidirectional"))
    )
    (net (code "69") (name "/RX3") (class "Default")
      (node (ref "GPS") (pin "2") (pinfunction "2_2") (pintype "passive"))
      (node (ref "U$1") (pin "RX3") (pinfunction "RX3_RX3") (pintype "bidirectional"))
    )
    (net (code "70") (name "/SCK") (class "Default")
      (node (ref "IMU") (pin "5") (pinfunction "5_5") (pintype "passive"))
      (node (ref "RS") (pin "5") (pinfunction "5_5") (pintype "passive"))
      (node (ref "U$1") (pin "SCK_ICSP") (pinfunction "SCK_ICSP_SCK_ICSP") (pintype "bidirectional"))
    )
    (net (code "71") (name "/TX0") (class "Default")
      (node (ref "SPINS") (pin "2") (pinfunction "2_2") (pintype "passive"))
      (node (ref "U$1") (pin "TX0") (pinfunction "TX0_TX0") (pintype "bidirectional"))
    )
    (net (code "72") (name "/TX2") (class "Default")
      (node (ref "SPINS") (pin "4") (pinfunction "4_4") (pintype "passive"))
      (node (ref "U$1") (pin "TX2") (pinfunction "TX2_TX2") (pintype "bidirectional"))
    )
    (net (code "73") (name "/TX3") (class "Default")
      (node (ref "GPS") (pin "3") (pinfunction "3_3") (pintype "passive"))
      (node (ref "U$1") (pin "TX3") (pinfunction "TX3_TX3") (pintype "bidirectional"))
    )
    (net (code "74") (name "Net-(LED1-PadA)") (class "Default")
      (node (ref "LED1") (pin "A") (pinfunction "A_A") (pintype "passive"))
      (node (ref "R1") (pin "2") (pinfunction "2_2") (pintype "passive"))
    )
    (net (code "75") (name "Net-(LED2-PadA)") (class "Default")
      (node (ref "LED2") (pin "A") (pinfunction "A_A") (pintype "passive"))
      (node (ref "R2") (pin "2") (pinfunction "2_2") (pintype "passive"))
    )
    (net (code "76") (name "Net-(LED3-PadA)") (class "Default")
      (node (ref "LED3") (pin "A") (pinfunction "A_A") (pintype "passive"))
      (node (ref "R3") (pin "2") (pinfunction "2_2") (pintype "passive"))
    )
    (net (code "77") (name "Net-(LED4-PadA)") (class "Default")
      (node (ref "LED4") (pin "A") (pinfunction "A_A") (pintype "passive"))
      (node (ref "R19") (pin "2") (pinfunction "2_2") (pintype "passive"))
    )
    (net (code "78") (name "Net-(R2-Pad1)") (class "Default")
      (node (ref "R2") (pin "1") (pinfunction "1_1") (pintype "passive"))
      (node (ref "U$1") (pin "35") (pinfunction "35_35") (pintype "bidirectional"))
    )
    (net (code "79") (name "Net-(R3-Pad1)") (class "Default")
      (node (ref "R3") (pin "1") (pinfunction "1_1") (pintype "passive"))
      (node (ref "U$1") (pin "36") (pinfunction "36_36") (pintype "bidirectional"))
    )
    (net (code "80") (name "Net-(U$5-+IN)") (class "Default")
      (node (ref "R21") (pin "2") (pinfunction "2_2") (pintype "passive"))
      (node (ref "R22") (pin "1") (pinfunction "1_1") (pintype "passive"))
      (node (ref "U$5") (pin "12") (pinfunction "+IN_12") (pintype "bidirectional"))
    )
    (net (code "81") (name "Net-(U$5--IN)") (class "Default")
      (node (ref "U$5") (pin "10") (pinfunction "COMP_10") (pintype "bidirectional"))
      (node (ref "U$5") (pin "11") (pinfunction "-IN_11") (pintype "bidirectional"))
    )
    (net (code "82") (name "Net-(U$5-VREG1)") (class "Default")
      (node (ref "C30") (pin "1") (pinfunction "1_1") (pintype "passive"))
      (node (ref "U$5") (pin "3") (pinfunction "VREG1_3") (pintype "bidirectional"))
    )
    (net (code "83") (name "Net-(U$5-VREG2)") (class "Default")
      (node (ref "C32") (pin "1") (pinfunction "1_1") (pintype "passive"))
      (node (ref "U$5") (pin "14") (pinfunction "VREG2_14") (pintype "bidirectional"))
    )
    (net (code "84") (name "unconnected-(DC-CONV-Pad1)") (class "Default")
      (node (ref "DC-CONV") (pin "1") (pinfunction "1_1") (pintype "passive"))
    )
    (net (code "85") (name "unconnected-(DC-CONV-Pad3)") (class "Default")
      (node (ref "DC-CONV") (pin "3") (pinfunction "3_3") (pintype "passive"))
    )
    (net (code "86") (name "unconnected-(DC-CONV-Pad4)") (class "Default")
      (node (ref "DC-CONV") (pin "4") (pinfunction "4_4") (pintype "passive"))
    )
    (net (code "87") (name "unconnected-(DC-CONV-Pad5)") (class "Default")
      (node (ref "DC-CONV") (pin "5") (pinfunction "5_5") (pintype "passive"))
    )
    (net (code "88") (name "unconnected-(DC-CONV-Pad6)") (class "Default")
      (node (ref "DC-CONV") (pin "6") (pinfunction "6_6") (pintype "passive"))
    )
    (net (code "89") (name "unconnected-(DC-CONV-Pad7)") (class "Default")
      (node (ref "DC-CONV") (pin "7") (pinfunction "7_7") (pintype "passive"))
    )
    (net (code "90") (name "unconnected-(DC-CONV-Pad8)") (class "Default")
      (node (ref "DC-CONV") (pin "8") (pinfunction "8_8") (pintype "passive"))
    )
    (net (code "91") (name "unconnected-(DC-CONV-Pad9)") (class "Default")
      (node (ref "DC-CONV") (pin "9") (pinfunction "9_9") (pintype "passive"))
    )
    (net (code "92") (name "unconnected-(DC-CONV-Pad10)") (class "Default")
      (node (ref "DC-CONV") (pin "10") (pinfunction "10_10") (pintype "passive"))
    )
    (net (code "93") (name "unconnected-(DC-CONV-Pad11)") (class "Default")
      (node (ref "DC-CONV") (pin "11") (pinfunction "11_11") (pintype "passive"))
    )
    (net (code "94") (name "unconnected-(DC-CONV-Pad12)") (class "Default")
      (node (ref "DC-CONV") (pin "12") (pinfunction "12_12") (pintype "passive"))
    )
    (net (code "95") (name "unconnected-(DC-CONV-Pad13)") (class "Default")
      (node (ref "DC-CONV") (pin "13") (pinfunction "13_13") (pintype "passive"))
    )
    (net (code "96") (name "unconnected-(DC-CONV-Pad14)") (class "Default")
      (node (ref "DC-CONV") (pin "14") (pinfunction "14_14") (pintype "passive"))
    )
    (net (code "97") (name "unconnected-(DC-CONV-Pad15)") (class "Default")
      (node (ref "DC-CONV") (pin "15") (pinfunction "15_15") (pintype "passive"))
    )
    (net (code "98") (name "unconnected-(DC-CONV-Pad17)") (class "Default")
      (node (ref "DC-CONV") (pin "17") (pinfunction "17_17") (pintype "passive"))
    )
    (net (code "99") (name "unconnected-(DC-CONV-Pad18)") (class "Default")
      (node (ref "DC-CONV") (pin "18") (pinfunction "18_18") (pintype "passive"))
    )
    (net (code "100") (name "unconnected-(DC-CONV-Pad19)") (class "Default")
      (node (ref "DC-CONV") (pin "19") (pinfunction "19_19") (pintype "passive"))
    )
    (net (code "101") (name "unconnected-(DC-CONV-Pad20)") (class "Default")
      (node (ref "DC-CONV") (pin "20") (pinfunction "20_20") (pintype "passive"))
    )
    (net (code "102") (name "unconnected-(DC-CONV-Pad21)") (class "Default")
      (node (ref "DC-CONV") (pin "21") (pinfunction "21_21") (pintype "passive"))
    )
    (net (code "103") (name "unconnected-(DC-CONV-Pad22)") (class "Default")
      (node (ref "DC-CONV") (pin "22") (pinfunction "22_22") (pintype "passive"))
    )
    (net (code "104") (name "unconnected-(DC-CONV-Pad24)") (class "Default")
      (node (ref "DC-CONV") (pin "24") (pinfunction "24_24") (pintype "passive"))
    )
    (net (code "105") (name "unconnected-(LR1-DOUT-Pad13)") (class "Default")
      (node (ref "LR1") (pin "13") (pinfunction "DOUT_13") (pintype "output"))
    )
    (net (code "106") (name "unconnected-(LR1-~{EN}-Pad12)") (class "Default")
      (node (ref "LR1") (pin "12") (pinfunction "~{EN}_12") (pintype "input"))
    )
    (net (code "107") (name "unconnected-(LR2-DOUT-Pad13)") (class "Default")
      (node (ref "LR2") (pin "13") (pinfunction "DOUT_13") (pintype "output"))
    )
    (net (code "108") (name "unconnected-(LR2-~{EN}-Pad12)") (class "Default")
      (node (ref "LR2") (pin "12") (pinfunction "~{EN}_12") (pintype "input"))
    )
    (net (code "109") (name "unconnected-(U$1-Pad3)") (class "Default")
      (node (ref "U$1") (pin "3") (pinfunction "3_3") (pintype "bidirectional"))
    )
    (net (code "110") (name "unconnected-(U$1-Pad5V_A)") (class "Default")
      (node (ref "U$1") (pin "5V_A") (pinfunction "5V_A_5V_A") (pintype "bidirectional"))
    )
    (net (code "111") (name "unconnected-(U$1-Pad5V_B)") (class "Default")
      (node (ref "U$1") (pin "5V_B") (pinfunction "5V_B_5V_B") (pintype "bidirectional"))
    )
    (net (code "112") (name "unconnected-(U$1-Pad6)") (class "Default")
      (node (ref "U$1") (pin "6") (pinfunction "6_6") (pintype "bidirectional"))
    )
    (net (code "113") (name "unconnected-(U$1-Pad7)") (class "Default")
      (node (ref "U$1") (pin "7") (pinfunction "7_7") (pintype "bidirectional"))
    )
    (net (code "114") (name "unconnected-(U$1-Pad12)") (class "Default")
      (node (ref "U$1") (pin "12") (pinfunction "12_12") (pintype "bidirectional"))
    )
    (net (code "115") (name "unconnected-(U$1-Pad23)") (class "Default")
      (node (ref "U$1") (pin "23") (pinfunction "23_23") (pintype "bidirectional"))
    )
    (net (code "116") (name "unconnected-(U$1-Pad24)") (class "Default")
      (node (ref "U$1") (pin "24") (pinfunction "24_24") (pintype "bidirectional"))
    )
    (net (code "117") (name "unconnected-(U$1-Pad30)") (class "Default")
      (node (ref "U$1") (pin "30") (pinfunction "30_30") (pintype "bidirectional"))
    )
    (net (code "118") (name "unconnected-(U$1-Pad31)") (class "Default")
      (node (ref "U$1") (pin "31") (pinfunction "31_31") (pintype "bidirectional"))
    )
    (net (code "119") (name "unconnected-(U$1-Pad34)") (class "Default")
      (node (ref "U$1") (pin "34") (pinfunction "34_34") (pintype "bidirectional"))
    )
    (net (code "120") (name "unconnected-(U$1-Pad41)") (class "Default")
      (node (ref "U$1") (pin "41") (pinfunction "41_41") (pintype "bidirectional"))
    )
    (net (code "121") (name "unconnected-(U$1-Pad42)") (class "Default")
      (node (ref "U$1") (pin "42") (pinfunction "42_42") (pintype "bidirectional"))
    )
    (net (code "122") (name "unconnected-(U$1-Pad43)") (class "Default")
      (node (ref "U$1") (pin "43") (pinfunction "43_43") (pintype "bidirectional"))
    )
    (net (code "123") (name "unconnected-(U$1-Pad44)") (class "Default")
      (node (ref "U$1") (pin "44") (pinfunction "44_44") (pintype "bidirectional"))
    )
    (net (code "124") (name "unconnected-(U$1-Pad45)") (class "Default")
      (node (ref "U$1") (pin "45") (pinfunction "45_45") (pintype "bidirectional"))
    )
    (net (code "125") (name "unconnected-(U$1-PadA5)") (class "Default")
      (node (ref "U$1") (pin "A5") (pinfunction "A5_A5") (pintype "bidirectional"))
    )
    (net (code "126") (name "unconnected-(U$1-PadA10)") (class "Default")
      (node (ref "U$1") (pin "A10") (pinfunction "A10_A10") (pintype "bidirectional"))
    )
    (net (code "127") (name "unconnected-(U$1-PadAREF)") (class "Default")
      (node (ref "U$1") (pin "AREF") (pinfunction "AREF_AREF") (pintype "bidirectional"))
    )
    (net (code "128") (name "unconnected-(U$1-PadCANRX)") (class "Default")
      (node (ref "U$1") (pin "CANRX") (pinfunction "CANRX_CANRX") (pintype "bidirectional"))
    )
    (net (code "129") (name "unconnected-(U$1-PadCANTX)") (class "Default")
      (node (ref "U$1") (pin "CANTX") (pinfunction "CANTX_CANTX") (pintype "bidirectional"))
    )
    (net (code "130") (name "unconnected-(U$1-PadDAC0)") (class "Default")
      (node (ref "U$1") (pin "DAC0") (pinfunction "DAC0_DAC0") (pintype "bidirectional"))
    )
    (net (code "131") (name "unconnected-(U$1-PadDAC1)") (class "Default")
      (node (ref "U$1") (pin "DAC1") (pinfunction "DAC1_DAC1") (pintype "bidirectional"))
    )
    (net (code "132") (name "unconnected-(U$1-PadGND1)") (class "Default")
      (node (ref "U$1") (pin "GND1") (pinfunction "GND1_GND1") (pintype "bidirectional"))
    )
    (net (code "133") (name "unconnected-(U$1-PadGND_A)") (class "Default")
      (node (ref "U$1") (pin "GND_A") (pinfunction "GND_A_GND_A") (pintype "bidirectional"))
    )
    (net (code "134") (name "unconnected-(U$1-PadGND_B)") (class "Default")
      (node (ref "U$1") (pin "GND_B") (pinfunction "GND_B_GND_B") (pintype "bidirectional"))
    )
    (net (code "135") (name "unconnected-(U$1-PadGND_DEBUG)") (class "Default")
      (node (ref "U$1") (pin "GND_DEBUG") (pinfunction "GND_DEBUG_GND_DEBUG") (pintype "bidirectional"))
    )
    (net (code "136") (name "unconnected-(U$1-PadGND_ICSP)") (class "Default")
      (node (ref "U$1") (pin "GND_ICSP") (pinfunction "GND_ICSP_GND_ICSP") (pintype "bidirectional"))
    )
    (net (code "137") (name "unconnected-(U$1-PadIOREF)") (class "Default")
      (node (ref "U$1") (pin "IOREF") (pinfunction "IOREF_IOREF") (pintype "bidirectional"))
    )
    (net (code "138") (name "unconnected-(U$1-PadNC)") (class "Default")
      (node (ref "U$1") (pin "NC") (pinfunction "NC_NC") (pintype "bidirectional"))
    )
    (net (code "139") (name "unconnected-(U$1-PadRESET)") (class "Default")
      (node (ref "U$1") (pin "RESET") (pinfunction "RESET_RESET") (pintype "bidirectional"))
    )
    (net (code "140") (name "unconnected-(U$1-PadRESET_DEBUG)") (class "Default")
      (node (ref "U$1") (pin "RESET_DEBUG") (pinfunction "RESET_DEBUG_RESET_DEBUG") (pintype "bidirectional"))
    )
    (net (code "141") (name "unconnected-(U$1-PadRESET_ICSP)") (class "Default")
      (node (ref "U$1") (pin "RESET_ICSP") (pinfunction "RESET_ICSP_RESET_ICSP") (pintype "bidirectional"))
    )
    (net (code "142") (name "unconnected-(U$1-PadRX1)") (class "Default")
      (node (ref "U$1") (pin "RX1") (pinfunction "RX1_RX1") (pintype "bidirectional"))
    )
    (net (code "143") (name "unconnected-(U$1-PadSCL)") (class "Default")
      (node (ref "U$1") (pin "SCL") (pinfunction "SCL_SCL") (pintype "bidirectional"))
    )
    (net (code "144") (name "unconnected-(U$1-PadSCL1)") (class "Default")
      (node (ref "U$1") (pin "SCL1") (pinfunction "SCL1_SCL1") (pintype "bidirectional"))
    )
    (net (code "145") (name "unconnected-(U$1-PadSDA)") (class "Default")
      (node (ref "U$1") (pin "SDA") (pinfunction "SDA_SDA") (pintype "bidirectional"))
    )
    (net (code "146") (name "unconnected-(U$1-PadSDA1)") (class "Default")
      (node (ref "U$1") (pin "SDA1") (pinfunction "SDA1_SDA1") (pintype "bidirectional"))
    )
    (net (code "147") (name "unconnected-(U$1-PadSWCLK_DEBUG)") (class "Default")
      (node (ref "U$1") (pin "SWCLK_DEBUG") (pinfunction "SWCLK_DEBUG_SWCLK_DEBUG") (pintype "bidirectional"))
    )
    (net (code "148") (name "unconnected-(U$1-PadSWDIO_DEBUG)") (class "Default")
      (node (ref "U$1") (pin "SWDIO_DEBUG") (pinfunction "SWDIO_DEBUG_SWDIO_DEBUG") (pintype "bidirectional"))
    )
    (net (code "149") (name "unconnected-(U$1-PadTX1)") (class "Default")
      (node (ref "U$1") (pin "TX1") (pinfunction "TX1_TX1") (pintype "bidirectional"))
    )
    (net (code "150") (name "unconnected-(U$1-PadVIN)") (class "Default")
      (node (ref "U$1") (pin "VIN") (pinfunction "VIN_VIN") (pintype "bidirectional"))
    )
    (net (code "151") (name "unconnected-(U$5-EAOUT2-Pad6)") (class "Default")
      (node (ref "U$5") (pin "6") (pinfunction "EAOUT2_6") (pintype "bidirectional"))
    )
    (net (code "152") (name "unconnected-(U$5-NC2-Pad5)") (class "Default")
      (node (ref "U$5") (pin "5") (pinfunction "NC2_5") (pintype "bidirectional"))
    )
    (net (code "153") (name "unconnected-(U$5-REFOUT-Pad13)") (class "Default")
      (node (ref "U$5") (pin "13") (pinfunction "REFOUT_13") (pintype "bidirectional"))
    )
    (net (code "154") (name "unconnected-(U$5-REFOUT1-Pad4)") (class "Default")
      (node (ref "U$5") (pin "4") (pinfunction "REFOUT1_4") (pintype "bidirectional"))
    )
  )
)
